# PALVersion.net
KiCad netlist of a schematic drawn in EAGLE
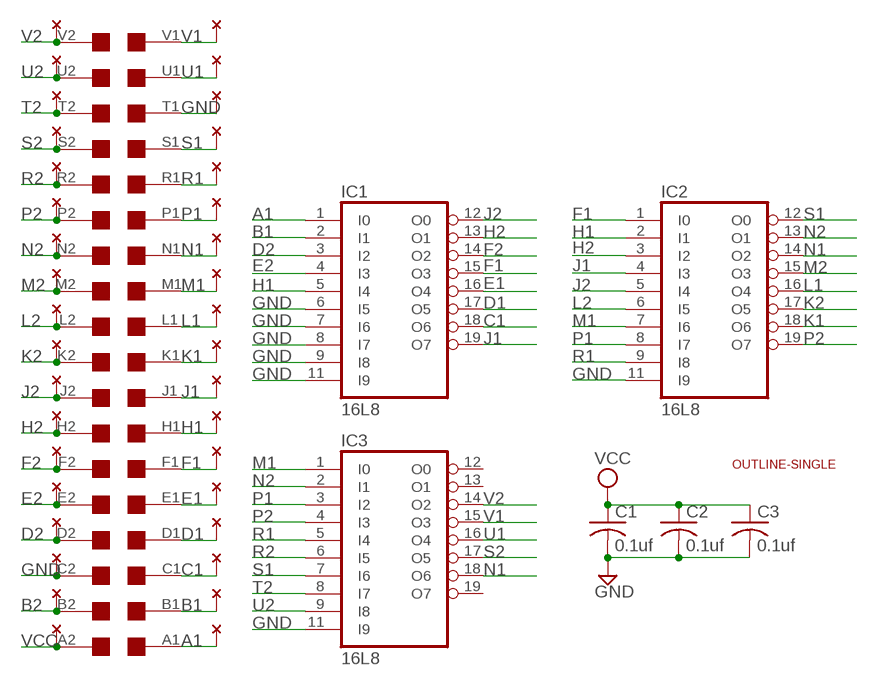
[diagram p0: schematic, sheet 1]

(export (version "E")
  (design (tool "Eeschema 10.0.6"))
  (components
    (comp (ref "C1")
      (value "0.1uf")
      (footprint "eagle-import:C050-025X075")
      (libsource (lib "eagle-import") (part "C-US050-025X075"))
    )
    (comp (ref "C2")
      (value "0.1uf")
      (footprint "eagle-import:C050-025X075")
      (libsource (lib "eagle-import") (part "C-US050-025X075"))
    )
    (comp (ref "C3")
      (value "0.1uf")
      (footprint "eagle-import:C050-025X075")
      (libsource (lib "eagle-import") (part "C-US050-025X075"))
    )
    (comp (ref "IC1")
      (value "16L8")
      (footprint "eagle-import:DIL20")
      (fields (field (name "MF") "TEXAS INSTRUMENTS") (field (name "MPN") "TIBPAL16L8-7CN"))
      (libsource (lib "eagle-import") (part "16L8"))
    )
    (comp (ref "IC2")
      (value "16L8")
      (footprint "eagle-import:DIL20")
      (fields (field (name "MF") "TEXAS INSTRUMENTS") (field (name "MPN") "TIBPAL16L8-7CN"))
      (libsource (lib "eagle-import") (part "16L8"))
    )
    (comp (ref "IC3")
      (value "16L8")
      (footprint "eagle-import:DIL20")
      (fields (field (name "MF") "TEXAS INSTRUMENTS") (field (name "MPN") "TIBPAL16L8-7CN"))
      (libsource (lib "eagle-import") (part "16L8"))
    )
    (comp (ref "U$1")
      (value "EDGE-2CONNECTOR")
      (footprint "eagle-import:EDGE-CON2")
      (libsource (lib "eagle-import") (part "EDGE-2CONNECTOR"))
    )
    (comp (ref "U$4")
      (value "THRU-HOLE2A")
      (footprint "eagle-import:THRU-HOLEA")
      (libsource (lib "eagle-import") (part "THRU-HOLE2A"))
    )
    (comp (ref "U$5")
      (value "OUTLINE-SINGLE")
      (footprint "eagle-import:SINGLE")
      (libsource (lib "eagle-import") (part "OUTLINE-SINGLE"))
    )
  )
  (nets
    (net (code "1") (name "/A1") (class "Default")
      (node (ref "IC1") (pin "1") (pinfunction "I0_1") (pintype "input"))
      (node (ref "U$1") (pin "A1") (pinfunction "1_A1") (pintype "bidirectional"))
      (node (ref "U$4") (pin "A1") (pinfunction "P$1_A1") (pintype "passive"))
    )
    (net (code "2") (name "/B1") (class "Default")
      (node (ref "IC1") (pin "2") (pinfunction "I1_2") (pintype "input"))
      (node (ref "U$1") (pin "B1") (pinfunction "1_B1") (pintype "bidirectional"))
      (node (ref "U$4") (pin "B1") (pinfunction "P$1_B1") (pintype "passive"))
    )
    (net (code "3") (name "/B2") (class "Default")
      (node (ref "U$1") (pin "B2") (pinfunction "1_B2") (pintype "bidirectional"))
      (node (ref "U$4") (pin "B2") (pinfunction "P$1_B2") (pintype "passive"))
    )
    (net (code "4") (name "/C1") (class "Default")
      (node (ref "IC1") (pin "18") (pinfunction "O6_18") (pintype "bidirectional"))
      (node (ref "U$1") (pin "C1") (pinfunction "1_C1") (pintype "bidirectional"))
      (node (ref "U$4") (pin "C1") (pinfunction "P$1_C1") (pintype "passive"))
    )
    (net (code "5") (name "/D1") (class "Default")
      (node (ref "IC1") (pin "17") (pinfunction "O5_17") (pintype "bidirectional"))
      (node (ref "U$1") (pin "D1") (pinfunction "1_D1") (pintype "bidirectional"))
      (node (ref "U$4") (pin "D1") (pinfunction "P$1_D1") (pintype "passive"))
    )
    (net (code "6") (name "/D2") (class "Default")
      (node (ref "IC1") (pin "3") (pinfunction "I2_3") (pintype "input"))
      (node (ref "U$1") (pin "D2") (pinfunction "1_D2") (pintype "bidirectional"))
      (node (ref "U$4") (pin "D2") (pinfunction "P$1_D2") (pintype "passive"))
    )
    (net (code "7") (name "/E1") (class "Default")
      (node (ref "IC1") (pin "16") (pinfunction "O4_16") (pintype "bidirectional"))
      (node (ref "U$1") (pin "E1") (pinfunction "1_E1") (pintype "bidirectional"))
      (node (ref "U$4") (pin "E1") (pinfunction "P$1_E1") (pintype "passive"))
    )
    (net (code "8") (name "/E2") (class "Default")
      (node (ref "IC1") (pin "4") (pinfunction "I3_4") (pintype "input"))
      (node (ref "U$1") (pin "E2") (pinfunction "1_E2") (pintype "bidirectional"))
      (node (ref "U$4") (pin "E2") (pinfunction "P$1_E2") (pintype "passive"))
    )
    (net (code "9") (name "/F1") (class "Default")
      (node (ref "IC1") (pin "15") (pinfunction "O3_15") (pintype "bidirectional"))
      (node (ref "IC2") (pin "1") (pinfunction "I0_1") (pintype "input"))
      (node (ref "U$1") (pin "F1") (pinfunction "1_F1") (pintype "bidirectional"))
      (node (ref "U$4") (pin "F1") (pinfunction "P$1_F1") (pintype "passive"))
    )
    (net (code "10") (name "/F2") (class "Default")
      (node (ref "IC1") (pin "14") (pinfunction "O2_14") (pintype "bidirectional"))
      (node (ref "U$1") (pin "F2") (pinfunction "1_F2") (pintype "bidirectional"))
      (node (ref "U$4") (pin "F2") (pinfunction "P$1_F2") (pintype "passive"))
    )
    (net (code "11") (name "/H1") (class "Default")
      (node (ref "IC1") (pin "5") (pinfunction "I4_5") (pintype "input"))
      (node (ref "IC2") (pin "2") (pinfunction "I1_2") (pintype "input"))
      (node (ref "U$1") (pin "H1") (pinfunction "1_H1") (pintype "bidirectional"))
      (node (ref "U$4") (pin "H1") (pinfunction "P$1_H1") (pintype "passive"))
    )
    (net (code "12") (name "/H2") (class "Default")
      (node (ref "IC1") (pin "13") (pinfunction "O1_13") (pintype "bidirectional"))
      (node (ref "IC2") (pin "3") (pinfunction "I2_3") (pintype "input"))
      (node (ref "U$1") (pin "H2") (pinfunction "1_H2") (pintype "bidirectional"))
      (node (ref "U$4") (pin "H2") (pinfunction "P$1_H2") (pintype "passive"))
    )
    (net (code "13") (name "/J1") (class "Default")
      (node (ref "IC1") (pin "19") (pinfunction "O7_19") (pintype "output"))
      (node (ref "IC2") (pin "4") (pinfunction "I3_4") (pintype "input"))
      (node (ref "U$1") (pin "J1") (pinfunction "1_J1") (pintype "bidirectional"))
      (node (ref "U$4") (pin "J1") (pinfunction "P$1_J1") (pintype "passive"))
    )
    (net (code "14") (name "/J2") (class "Default")
      (node (ref "IC1") (pin "12") (pinfunction "O0_12") (pintype "output"))
      (node (ref "IC2") (pin "5") (pinfunction "I4_5") (pintype "input"))
      (node (ref "U$1") (pin "J2") (pinfunction "1_J2") (pintype "bidirectional"))
      (node (ref "U$4") (pin "J2") (pinfunction "P$1_J2") (pintype "passive"))
    )
    (net (code "15") (name "/K1") (class "Default")
      (node (ref "IC2") (pin "18") (pinfunction "O6_18") (pintype "bidirectional"))
      (node (ref "U$1") (pin "K1") (pinfunction "1_K1") (pintype "bidirectional"))
      (node (ref "U$4") (pin "K1") (pinfunction "P$1_K1") (pintype "passive"))
    )
    (net (code "16") (name "/K2") (class "Default")
      (node (ref "IC2") (pin "17") (pinfunction "O5_17") (pintype "bidirectional"))
      (node (ref "U$1") (pin "K2") (pinfunction "1_K2") (pintype "bidirectional"))
      (node (ref "U$4") (pin "K2") (pinfunction "P$1_K2") (pintype "passive"))
    )
    (net (code "17") (name "/L1") (class "Default")
      (node (ref "IC2") (pin "16") (pinfunction "O4_16") (pintype "bidirectional"))
      (node (ref "U$1") (pin "L1") (pinfunction "1_L1") (pintype "bidirectional"))
      (node (ref "U$4") (pin "L1") (pinfunction "P$1_L1") (pintype "passive"))
    )
    (net (code "18") (name "/L2") (class "Default")
      (node (ref "IC2") (pin "6") (pinfunction "I5_6") (pintype "input"))
      (node (ref "U$1") (pin "L2") (pinfunction "1_L2") (pintype "bidirectional"))
      (node (ref "U$4") (pin "L2") (pinfunction "P$1_L2") (pintype "passive"))
    )
    (net (code "19") (name "/M1") (class "Default")
      (node (ref "IC2") (pin "7") (pinfunction "I6_7") (pintype "input"))
      (node (ref "IC3") (pin "1") (pinfunction "I0_1") (pintype "input"))
      (node (ref "U$1") (pin "M1") (pinfunction "1_M1") (pintype "bidirectional"))
      (node (ref "U$4") (pin "M1") (pinfunction "P$1_M1") (pintype "passive"))
    )
    (net (code "20") (name "/M2") (class "Default")
      (node (ref "IC2") (pin "15") (pinfunction "O3_15") (pintype "bidirectional"))
      (node (ref "U$1") (pin "M2") (pinfunction "1_M2") (pintype "bidirectional"))
      (node (ref "U$4") (pin "M2") (pinfunction "P$1_M2") (pintype "passive"))
    )
    (net (code "21") (name "/N1") (class "Default")
      (node (ref "IC2") (pin "14") (pinfunction "O2_14") (pintype "bidirectional"))
      (node (ref "IC3") (pin "18") (pinfunction "O6_18") (pintype "bidirectional"))
      (node (ref "U$1") (pin "N1") (pinfunction "1_N1") (pintype "bidirectional"))
      (node (ref "U$4") (pin "N1") (pinfunction "P$1_N1") (pintype "passive"))
    )
    (net (code "22") (name "/N2") (class "Default")
      (node (ref "IC2") (pin "13") (pinfunction "O1_13") (pintype "bidirectional"))
      (node (ref "IC3") (pin "2") (pinfunction "I1_2") (pintype "input"))
      (node (ref "U$1") (pin "N2") (pinfunction "1_N2") (pintype "bidirectional"))
      (node (ref "U$4") (pin "N2") (pinfunction "P$1_N2") (pintype "passive"))
    )
    (net (code "23") (name "/P1") (class "Default")
      (node (ref "IC2") (pin "8") (pinfunction "I7_8") (pintype "input"))
      (node (ref "IC3") (pin "3") (pinfunction "I2_3") (pintype "input"))
      (node (ref "U$1") (pin "P1") (pinfunction "1_P1") (pintype "bidirectional"))
      (node (ref "U$4") (pin "P1") (pinfunction "P$1_P1") (pintype "passive"))
    )
    (net (code "24") (name "/P2") (class "Default")
      (node (ref "IC2") (pin "19") (pinfunction "O7_19") (pintype "output"))
      (node (ref "IC3") (pin "4") (pinfunction "I3_4") (pintype "input"))
      (node (ref "U$1") (pin "P2") (pinfunction "1_P2") (pintype "bidirectional"))
      (node (ref "U$4") (pin "P2") (pinfunction "P$1_P2") (pintype "passive"))
    )
    (net (code "25") (name "/R1") (class "Default")
      (node (ref "IC2") (pin "9") (pinfunction "I8_9") (pintype "input"))
      (node (ref "IC3") (pin "5") (pinfunction "I4_5") (pintype "input"))
      (node (ref "U$1") (pin "R1") (pinfunction "1_R1") (pintype "bidirectional"))
      (node (ref "U$4") (pin "R1") (pinfunction "P$1_R1") (pintype "passive"))
    )
    (net (code "26") (name "/R2") (class "Default")
      (node (ref "IC3") (pin "6") (pinfunction "I5_6") (pintype "input"))
      (node (ref "U$1") (pin "R2") (pinfunction "1_R2") (pintype "bidirectional"))
      (node (ref "U$4") (pin "R2") (pinfunction "P$1_R2") (pintype "passive"))
    )
    (net (code "27") (name "/S1") (class "Default")
      (node (ref "IC2") (pin "12") (pinfunction "O0_12") (pintype "output"))
      (node (ref "IC3") (pin "7") (pinfunction "I6_7") (pintype "input"))
      (node (ref "U$1") (pin "S1") (pinfunction "1_S1") (pintype "bidirectional"))
      (node (ref "U$4") (pin "S1") (pinfunction "P$1_S1") (pintype "passive"))
    )
    (net (code "28") (name "/S2") (class "Default")
      (node (ref "IC3") (pin "17") (pinfunction "O5_17") (pintype "bidirectional"))
      (node (ref "U$1") (pin "S2") (pinfunction "1_S2") (pintype "bidirectional"))
      (node (ref "U$4") (pin "S2") (pinfunction "P$1_S2") (pintype "passive"))
    )
    (net (code "29") (name "/T2") (class "Default")
      (node (ref "IC3") (pin "8") (pinfunction "I7_8") (pintype "input"))
      (node (ref "U$1") (pin "T2") (pinfunction "1_T2") (pintype "bidirectional"))
      (node (ref "U$4") (pin "T2") (pinfunction "P$1_T2") (pintype "passive"))
    )
    (net (code "30") (name "/U1") (class "Default")
      (node (ref "IC3") (pin "16") (pinfunction "O4_16") (pintype "bidirectional"))
      (node (ref "U$1") (pin "U1") (pinfunction "1_U1") (pintype "bidirectional"))
      (node (ref "U$4") (pin "U1") (pinfunction "P$1_U1") (pintype "passive"))
    )
    (net (code "31") (name "/U2") (class "Default")
      (node (ref "IC3") (pin "9") (pinfunction "I8_9") (pintype "input"))
      (node (ref "U$1") (pin "U2") (pinfunction "1_U2") (pintype "bidirectional"))
      (node (ref "U$4") (pin "U2") (pinfunction "P$1_U2") (pintype "passive"))
    )
    (net (code "32") (name "/V1") (class "Default")
      (node (ref "IC3") (pin "15") (pinfunction "O3_15") (pintype "bidirectional"))
      (node (ref "U$1") (pin "V1") (pinfunction "1_V1") (pintype "bidirectional"))
      (node (ref "U$4") (pin "V1") (pinfunction "P$1_V1") (pintype "passive"))
    )
    (net (code "33") (name "/V2") (class "Default")
      (node (ref "IC3") (pin "14") (pinfunction "O2_14") (pintype "bidirectional"))
      (node (ref "U$1") (pin "V2") (pinfunction "1_V2") (pintype "bidirectional"))
      (node (ref "U$4") (pin "V2") (pinfunction "P$1_V2") (pintype "passive"))
    )
    (net (code "34") (name "GND") (class "Default")
      (node (ref "C1") (pin "2") (pinfunction "2_2") (pintype "passive"))
      (node (ref "C2") (pin "2") (pinfunction "2_2") (pintype "passive"))
      (node (ref "C3") (pin "2") (pinfunction "2_2") (pintype "passive"))
      (node (ref "IC1") (pin "11") (pinfunction "I9_11") (pintype "input"))
      (node (ref "IC1") (pin "6") (pinfunction "I5_6") (pintype "input"))
      (node (ref "IC1") (pin "7") (pinfunction "I6_7") (pintype "input"))
      (node (ref "IC1") (pin "8") (pinfunction "I7_8") (pintype "input"))
      (node (ref "IC1") (pin "9") (pinfunction "I8_9") (pintype "input"))
      (node (ref "IC2") (pin "11") (pinfunction "I9_11") (pintype "input"))
      (node (ref "IC3") (pin "11") (pinfunction "I9_11") (pintype "input"))
      (node (ref "U$1") (pin "C2") (pinfunction "1_C2") (pintype "bidirectional"))
      (node (ref "U$1") (pin "T1") (pinfunction "1_T1") (pintype "bidirectional"))
      (node (ref "U$4") (pin "C2") (pinfunction "P$1_C2") (pintype "passive"))
      (node (ref "U$4") (pin "T1") (pinfunction "P$1_T1") (pintype "passive"))
    )
    (net (code "35") (name "VCC") (class "Default")
      (node (ref "C1") (pin "1") (pinfunction "1_1") (pintype "passive"))
      (node (ref "C2") (pin "1") (pinfunction "1_1") (pintype "passive"))
      (node (ref "C3") (pin "1") (pinfunction "1_1") (pintype "passive"))
      (node (ref "U$1") (pin "A2") (pinfunction "1_A2") (pintype "bidirectional"))
      (node (ref "U$4") (pin "A2") (pinfunction "P$1_A2") (pintype "passive"))
    )
    (net (code "36") (name "unconnected-(IC3A-O0-Pad12)") (class "Default")
      (node (ref "IC3") (pin "12") (pinfunction "O0_12") (pintype "output"))
    )
    (net (code "37") (name "unconnected-(IC3A-O1-Pad13)") (class "Default")
      (node (ref "IC3") (pin "13") (pinfunction "O1_13") (pintype "bidirectional"))
    )
    (net (code "38") (name "unconnected-(IC3A-O7-Pad19)") (class "Default")
      (node (ref "IC3") (pin "19") (pinfunction "O7_19") (pintype "output"))
    )
  )
)
